# L298N.net
KiCad netlist of a schematic drawn in Altium Designer
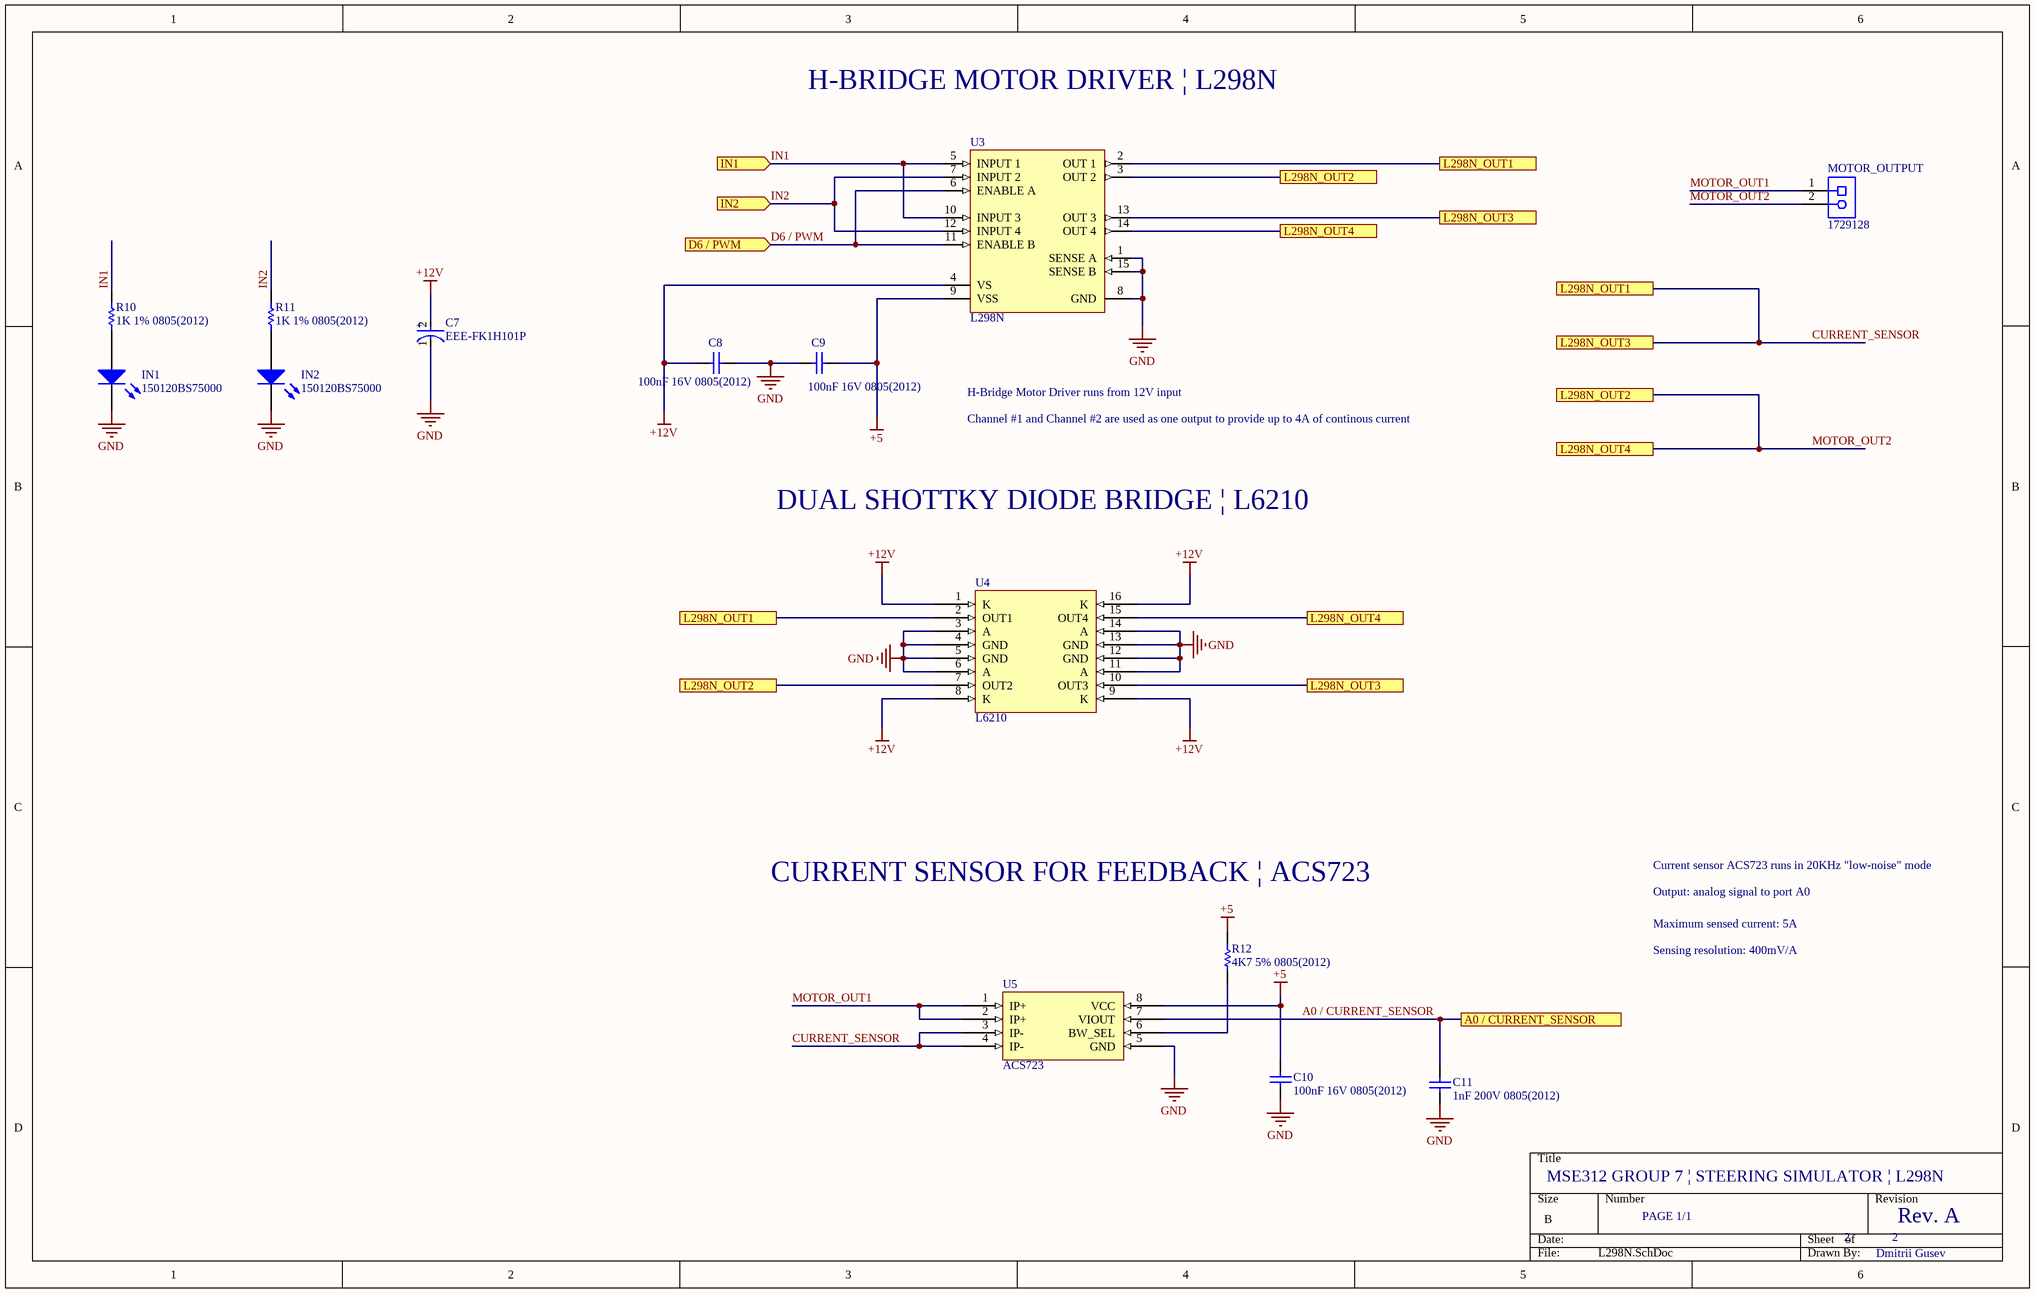
[diagram p0: L298N.SchDoc]

(export (version "E")
  (design (tool "Eeschema 10.0.6"))
  (components
    (comp (ref "C7")
      (value "EEE-FK1H101P")
      (footprint "FP-EEE-FK1H101P-MFG")
      (description "CAP ALUM 100UF 20% 50V SMD")
      (fields
        (field (name "TOLERANCE") "20%")
        (field (name "OCTOPART") "https://octopart.com/eeefk1h101p-panasonic-4642841")
      )
      (libsource (lib "Altium Content Vault") (part "cf48714ba7e38822c1575c7ec0b6d1f"))
    )
    (comp (ref "C8")
      (value "100nF 16V 0805(2012)")
      (footprint "CAPC0805(2012)100_L")
      (description "CAP 100nF 16V ±5% 0805 (2012 Metric) Thickness 1mm SMD")
      (fields (field (name "TOLERANCE") "Â±5%"))
      (libsource (lib "Altium Content Vault") (part "CAP"))
    )
    (comp (ref "C9")
      (value "100nF 16V 0805(2012)")
      (footprint "CAPC0805(2012)100_L")
      (description "CAP 100nF 16V ±5% 0805 (2012 Metric) Thickness 1mm SMD")
      (fields (field (name "TOLERANCE") "Â±5%"))
      (libsource (lib "Altium Content Vault") (part "CAP"))
    )
    (comp (ref "C10")
      (value "100nF 16V 0805(2012)")
      (footprint "CAPC0805(2012)100_L")
      (description "CAP 100nF 16V ±5% 0805 (2012 Metric) Thickness 1mm SMD")
      (fields (field (name "TOLERANCE") "Â±5%"))
      (libsource (lib "Altium Content Vault") (part "CAP"))
    )
    (comp (ref "C11")
      (value "1nF 200V 0805(2012)")
      (footprint "CAPC0805(2012)145_L")
      (description "CAP 1nF 200V ±10% 0805 (2012 Metric) Thickness 1.45mm SMD")
      (fields (field (name "TOLERANCE") "Â±10%"))
      (libsource (lib "Altium Content Vault") (part "CAP"))
    )
    (comp (ref "IN1")
      (value "150120BS75000")
      (footprint "1206_A")
      (description "SMD mono-color Chip LED, WL-SMCW, Blue")
      (fields (field (name "MANUFACTURER") "Wuerth Elektronik"))
      (libsource (lib "Altium Content Vault") (part "WE-LED_K1A2-2"))
    )
    (comp (ref "IN2")
      (value "150120BS75000")
      (footprint "1206_A")
      (description "SMD mono-color Chip LED, WL-SMCW, Blue")
      (fields (field (name "MANUFACTURER") "Wuerth Elektronik"))
      (libsource (lib "Altium Content Vault") (part "WE-LED_K1A2-2"))
    )
    (comp (ref "MOTOR_OUTPUT")
      (value "1729128")
      (footprint "PHOE-1729128-2_V")
      (description "PCB Terminal Block, 13.5 A, 400 V, 2-Pin THD, RoHS, Bulk")
      (fields (field (name "MANUFACTURER") "Phoenix Contact"))
      (libsource (lib "Altium Content Vault") (part "CN-2P-F-R2"))
    )
    (comp (ref "R10")
      (value "1K 1% 0805(2012)")
      (footprint "RESC0805(2012)_M")
      (description "1K 0.125W 1% 0805 (2012 Metric)  SMD")
      (fields (field (name "TOLERANCE") "1 %") (field (name "POWER") "0.125 W"))
      (libsource (lib "Altium Content Vault") (part "RES"))
    )
    (comp (ref "R11")
      (value "1K 1% 0805(2012)")
      (footprint "RESC0805(2012)_M")
      (description "1K 0.125W 1% 0805 (2012 Metric)  SMD")
      (fields (field (name "TOLERANCE") "1 %") (field (name "POWER") "0.125 W"))
      (libsource (lib "Altium Content Vault") (part "RES"))
    )
    (comp (ref "R12")
      (value "4K7 5% 0805(2012)")
      (footprint "RESC0805(2012)_N")
      (description "4K7 0.125W 5% 0805 (2012 Metric)  SMD")
      (fields (field (name "POWER") "0.125 W") (field (name "TOLERANCE") "5 %"))
      (libsource (lib "Altium Content Vault") (part "RES"))
    )
    (comp (ref "U3")
      (value "L298N")
      (footprint "STM-FM-15")
      (description "Dual Full-Bridge Driver, 4.8 to 46 V, -40 to 150 degC, 15-Pin FM (MW 15L), RoHS, Tube")
      (fields (field (name "MANUFACTURER") "STMicroelectronics") (field (name "PARTNUMBER") "L298"))
      (libsource (lib "Altium Content Vault") (part "STM-L298-15"))
    )
    (comp (ref "U4") (value "L6210") (footprint "L6210") (libsource (lib "MSE312_SIMRACER") (part "L6210")))
    (comp (ref "U5")
      (value "ACS723")
      (footprint "ACS723")
      (libsource (lib "MSE312_SIMRACER") (part "ACS723"))
    )
  )
  (nets
    (net (code "1") (name "+5") (class "Default")
      (node (ref "C10") (pin "2") (pinfunction "2_2") (pintype "passive"))
      (node (ref "C9") (pin "2") (pinfunction "2_2") (pintype "passive"))
      (node (ref "R12") (pin "2") (pinfunction "2_2") (pintype "passive"))
      (node (ref "U3") (pin "9") (pinfunction "VSS_9") (pintype "power_in"))
      (node (ref "U5") (pin "8") (pinfunction "VCC_8") (pintype "input"))
    )
    (net (code "2") (name "+12V") (class "Default")
      (node (ref "C7") (pin "2") (pinfunction "A_2") (pintype "passive"))
      (node (ref "C8") (pin "1") (pinfunction "1_1") (pintype "passive"))
      (node (ref "U3") (pin "4") (pinfunction "VS_4") (pintype "power_in"))
      (node (ref "U4") (pin "1") (pinfunction "K_1") (pintype "input"))
      (node (ref "U4") (pin "16") (pinfunction "K_16") (pintype "input"))
      (node (ref "U4") (pin "8") (pinfunction "K_8") (pintype "input"))
      (node (ref "U4") (pin "9") (pinfunction "K_9") (pintype "input"))
    )
    (net (code "3") (name "/A0 {slash} CURRENT_SENSOR") (class "Default")
      (node (ref "C11") (pin "2") (pinfunction "2_2") (pintype "passive"))
      (node (ref "U5") (pin "7") (pinfunction "VIOUT_7") (pintype "input"))
    )
    (net (code "4") (name "/CURRENT_SENSOR") (class "Default")
      (node (ref "U3") (pin "13") (pinfunction "OUT_3_13") (pintype "output"))
      (node (ref "U3") (pin "2") (pinfunction "OUT_1_2") (pintype "output"))
      (node (ref "U4") (pin "10") (pinfunction "OUT3_10") (pintype "input"))
      (node (ref "U4") (pin "2") (pinfunction "OUT1_2") (pintype "input"))
      (node (ref "U5") (pin "3") (pinfunction "IP-_3") (pintype "input"))
      (node (ref "U5") (pin "4") (pinfunction "IP-_4") (pintype "input"))
    )
    (net (code "5") (name "/D6 {slash} PWM") (class "Default")
      (node (ref "U3") (pin "11") (pinfunction "ENABLE_B_11") (pintype "input"))
      (node (ref "U3") (pin "6") (pinfunction "ENABLE_A_6") (pintype "input"))
    )
    (net (code "6") (name "/IN1") (class "Default")
      (node (ref "R10") (pin "2") (pinfunction "2_2") (pintype "passive"))
      (node (ref "U3") (pin "10") (pinfunction "INPUT_3_10") (pintype "input"))
      (node (ref "U3") (pin "5") (pinfunction "INPUT_1_5") (pintype "input"))
    )
    (net (code "7") (name "/IN2") (class "Default")
      (node (ref "R11") (pin "2") (pinfunction "2_2") (pintype "passive"))
      (node (ref "U3") (pin "12") (pinfunction "INPUT_4_12") (pintype "input"))
      (node (ref "U3") (pin "7") (pinfunction "INPUT_2_7") (pintype "input"))
    )
    (net (code "8") (name "/MOTOR_OUT1") (class "Default")
      (node (ref "MOTOR_OUTPUT") (pin "1") (pinfunction "1_1") (pintype "passive"))
      (node (ref "U5") (pin "1") (pinfunction "IP+_1") (pintype "input"))
      (node (ref "U5") (pin "2") (pinfunction "IP+_2") (pintype "input"))
    )
    (net (code "9") (name "/MOTOR_OUT2") (class "Default")
      (node (ref "MOTOR_OUTPUT") (pin "2") (pinfunction "2_2") (pintype "passive"))
      (node (ref "U3") (pin "14") (pinfunction "OUT_4_14") (pintype "output"))
      (node (ref "U3") (pin "3") (pinfunction "OUT_2_3") (pintype "output"))
      (node (ref "U4") (pin "15") (pinfunction "OUT4_15") (pintype "input"))
      (node (ref "U4") (pin "7") (pinfunction "OUT2_7") (pintype "input"))
    )
    (net (code "10") (name "GND") (class "Default")
      (node (ref "C10") (pin "1") (pinfunction "1_1") (pintype "passive"))
      (node (ref "C11") (pin "1") (pinfunction "1_1") (pintype "passive"))
      (node (ref "C7") (pin "1") (pinfunction "C_1") (pintype "passive"))
      (node (ref "C8") (pin "2") (pinfunction "2_2") (pintype "passive"))
      (node (ref "C9") (pin "1") (pinfunction "1_1") (pintype "passive"))
      (node (ref "IN1") (pin "1") (pinfunction "K_1") (pintype "passive"))
      (node (ref "IN2") (pin "1") (pinfunction "K_1") (pintype "passive"))
      (node (ref "U3") (pin "1") (pinfunction "SENSE_A_1") (pintype "input"))
      (node (ref "U3") (pin "15") (pinfunction "SENSE_B_15") (pintype "input"))
      (node (ref "U3") (pin "8") (pinfunction "GND_8") (pintype "power_in"))
      (node (ref "U4") (pin "11") (pinfunction "A_11") (pintype "input"))
      (node (ref "U4") (pin "12") (pinfunction "GND_12") (pintype "input"))
      (node (ref "U4") (pin "13") (pinfunction "GND_13") (pintype "input"))
      (node (ref "U4") (pin "14") (pinfunction "A_14") (pintype "input"))
      (node (ref "U4") (pin "3") (pinfunction "A_3") (pintype "input"))
      (node (ref "U4") (pin "4") (pinfunction "GND_4") (pintype "input"))
      (node (ref "U4") (pin "5") (pinfunction "GND_5") (pintype "input"))
      (node (ref "U4") (pin "6") (pinfunction "A_6") (pintype "input"))
      (node (ref "U5") (pin "5") (pinfunction "GND_5") (pintype "input"))
    )
    (net (code "11") (name "Net-(IN1-A)") (class "Default")
      (node (ref "IN1") (pin "2") (pinfunction "A_2") (pintype "passive"))
      (node (ref "R10") (pin "1") (pinfunction "1_1") (pintype "passive"))
    )
    (net (code "12") (name "Net-(IN2-A)") (class "Default")
      (node (ref "IN2") (pin "2") (pinfunction "A_2") (pintype "passive"))
      (node (ref "R11") (pin "1") (pinfunction "1_1") (pintype "passive"))
    )
    (net (code "13") (name "Net-(U5-BW_SEL)") (class "Default")
      (node (ref "R12") (pin "1") (pinfunction "1_1") (pintype "passive"))
      (node (ref "U5") (pin "6") (pinfunction "BW_SEL_6") (pintype "input"))
    )
  )
)
